# main.net
KiCad netlist of a schematic drawn in Altium Designer
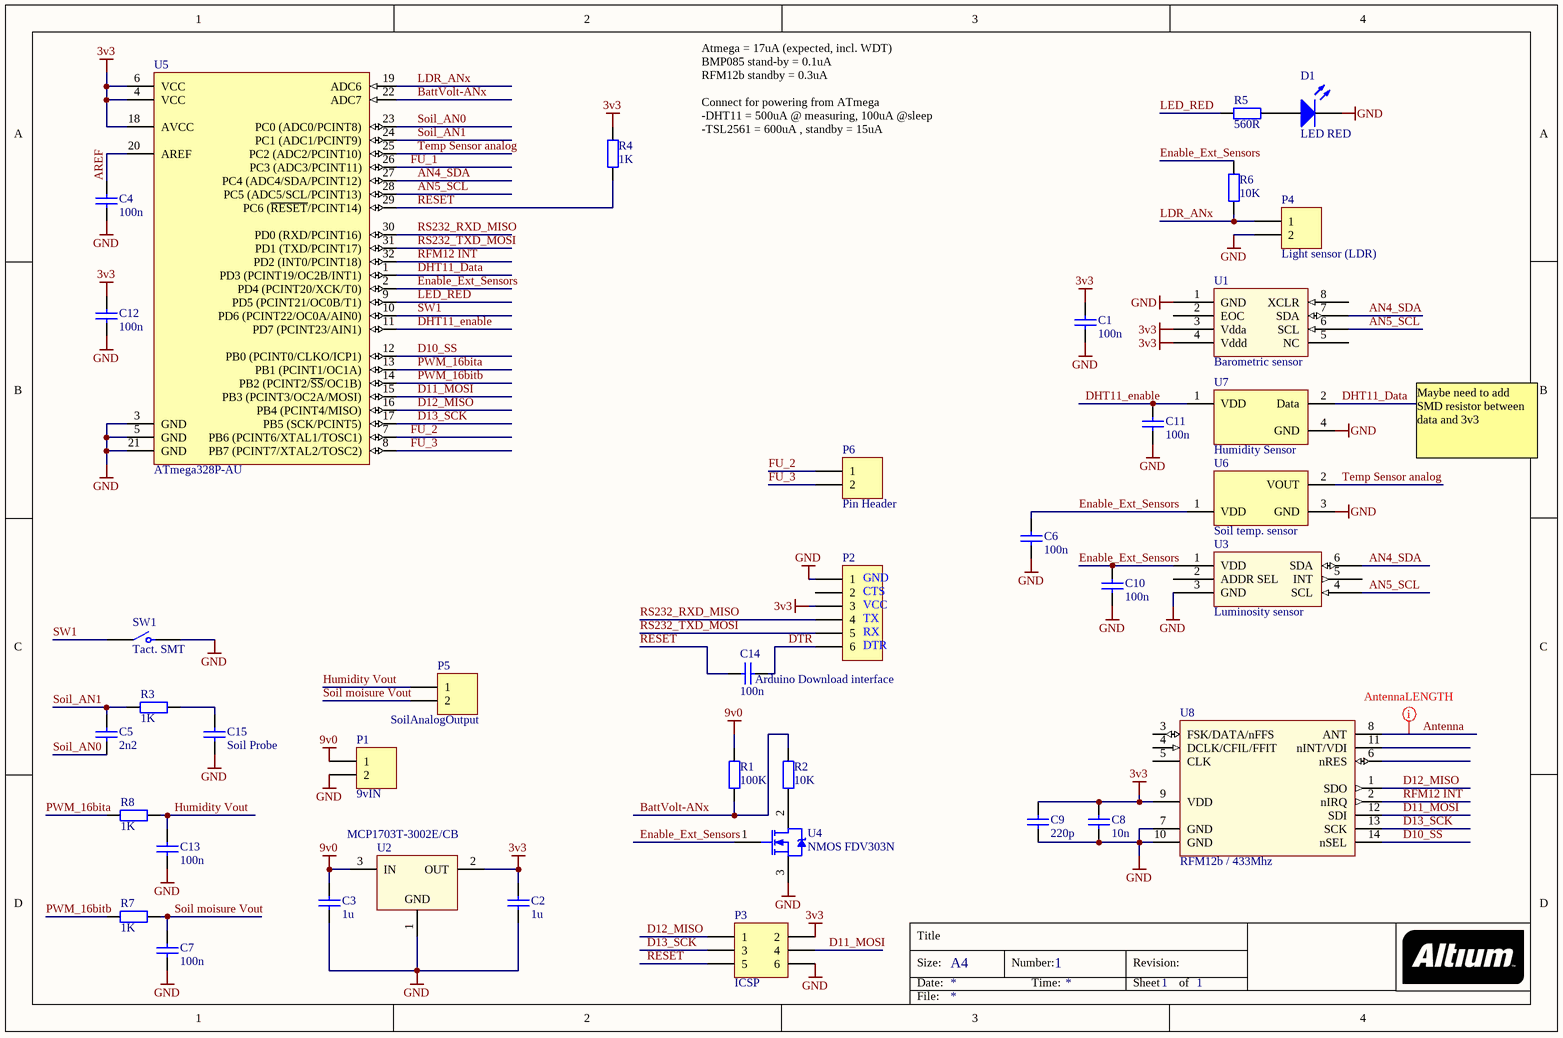
[diagram p0: main.SchDoc]

(export (version "E")
  (design (tool "Eeschema 10.0.6"))
  (components
    (comp (ref "C1") (value "100n") (footprint "C0805") (libsource (lib "OurDb") (part "cap_NonPolar")))
    (comp (ref "C2") (value "1u") (footprint "C0805") (libsource (lib "OurDb") (part "cap_NonPolar")))
    (comp (ref "C3") (value "1u") (footprint "C0805") (libsource (lib "OurDb") (part "cap_NonPolar")))
    (comp (ref "C4") (value "100n") (footprint "C0805") (libsource (lib "OurDb") (part "cap_NonPolar")))
    (comp (ref "C5") (value "2n2") (footprint "C0805") (libsource (lib "OurDb") (part "cap_NonPolar")))
    (comp (ref "C6") (value "100n") (footprint "C0805") (libsource (lib "OurDb") (part "cap_NonPolar")))
    (comp (ref "C7") (value "100n") (footprint "C0805") (libsource (lib "OurDb") (part "cap_NonPolar")))
    (comp (ref "C8") (value "10n") (footprint "C0805") (libsource (lib "OurDb") (part "cap_NonPolar")))
    (comp (ref "C9") (value "220p") (footprint "C0805") (libsource (lib "OurDb") (part "cap_NonPolar")))
    (comp (ref "C10") (value "100n") (footprint "C0805") (libsource (lib "OurDb") (part "cap_NonPolar")))
    (comp (ref "C11") (value "100n") (footprint "C0805") (libsource (lib "OurDb") (part "cap_NonPolar")))
    (comp (ref "C12") (value "100n") (footprint "C0805") (libsource (lib "OurDb") (part "cap_NonPolar")))
    (comp (ref "C13") (value "100n") (footprint "C0805") (libsource (lib "OurDb") (part "cap_NonPolar")))
    (comp (ref "C14") (value "100n") (footprint "C0805") (libsource (lib "OurDb") (part "cap_NonPolar")))
    (comp (ref "C15")
      (value "Soil Probe")
      (footprint "C0805")
      (fields (field (name "PART NUMBER") "18p"))
      (libsource (lib "OurDb") (part "cap_NonPolar"))
    )
    (comp (ref "D1")
      (value "LED RED")
      (footprint "LED-3mm")
      (description "LED, Surface Mount LED Indicator")
      (fields (field (name "PART NUMBER") "Red-3mm"))
      (libsource (lib "OurDb") (part "LED_SINGLE"))
    )
    (comp (ref "P1")
      (value "9vIN")
      (footprint "PH1x2_2.54")
      (description "Con1x2")
      (fields (field (name "PART NUMBER") "PH1x2"))
      (libsource (lib "OurDb") (part "Con1x2"))
    )
    (comp (ref "P2")
      (value "Arduino Download interface")
      (footprint "PH1x6_2.54")
      (description "Con1x6")
      (fields (field (name "PART NUMBER") "PH1x6"))
      (libsource (lib "OurDb") (part "Con1x6"))
    )
    (comp (ref "P3")
      (value "ICSP")
      (footprint "PH2x3_2.54")
      (description "Header, 3-Pin, Dual row")
      (fields (field (name "PART NUMBER") "PH2x3"))
      (libsource (lib "OurDb") (part "Con2x3"))
    )
    (comp (ref "P4")
      (value "Light sensor (LDR)")
      (footprint "PH1x2_2.54")
      (description "Con1x2")
      (fields (field (name "PART NUMBER") "PH1x2"))
      (libsource (lib "OurDb") (part "Con1x2"))
    )
    (comp (ref "P5")
      (value "SoilAnalogOutput")
      (footprint "PH1x2_2.54")
      (description "Con1x2")
      (fields (field (name "PART NUMBER") "PH1x2"))
      (libsource (lib "OurDb") (part "Con1x2"))
    )
    (comp (ref "P6")
      (value "Pin Header")
      (footprint "PH1x2_2.54")
      (description "Con1x2")
      (fields (field (name "PART NUMBER") "PH1x2") (field (name "AUTHOR") "Willy Pietersz"))
      (libsource (lib "OurDb") (part "Con1x2"))
    )
    (comp (ref "R1")
      (value "RESISTOR")
      (footprint "R0805")
      (description "Resistor")
      (fields (field (name "PART NUMBER") "100K") (field (name "PUBLISHER") "Altium Limited"))
      (libsource (lib "OurDb") (part "RESISTOR"))
    )
    (comp (ref "R2")
      (value "RESISTOR")
      (footprint "R0805")
      (description "Resistor")
      (fields (field (name "PART NUMBER") "10K") (field (name "PUBLISHER") "Altium Limited"))
      (libsource (lib "") (part "RESISTOR_3"))
    )
    (comp (ref "R3")
      (value "RESISTOR")
      (footprint "R0805")
      (description "Resistor")
      (fields (field (name "PART NUMBER") "1K") (field (name "PUBLISHER") "Altium Limited"))
      (libsource (lib "") (part "RESISTOR_1"))
    )
    (comp (ref "R4")
      (value "RESISTOR")
      (footprint "R0805")
      (description "Resistor")
      (fields (field (name "PART NUMBER") "1K") (field (name "PUBLISHER") "Altium Limited"))
      (libsource (lib "OurDb") (part "RESISTOR"))
    )
    (comp (ref "R5")
      (value "RESISTOR")
      (footprint "R0805")
      (description "Resistor")
      (fields (field (name "PART NUMBER") "560R") (field (name "PUBLISHER") "Altium Limited"))
      (libsource (lib "") (part "RESISTOR_2"))
    )
    (comp (ref "R6")
      (value "RESISTOR")
      (footprint "R0805")
      (description "Resistor")
      (fields (field (name "PART NUMBER") "10K") (field (name "PUBLISHER") "Altium Limited"))
      (libsource (lib "OurDb") (part "RESISTOR"))
    )
    (comp (ref "R7")
      (value "RESISTOR")
      (footprint "R0805")
      (description "Resistor")
      (fields (field (name "PART NUMBER") "1K") (field (name "PUBLISHER") "Altium Limited"))
      (libsource (lib "") (part "RESISTOR_1"))
    )
    (comp (ref "R8")
      (value "RESISTOR")
      (footprint "R0805")
      (description "Resistor")
      (fields (field (name "PART NUMBER") "1K") (field (name "PUBLISHER") "Altium Limited"))
      (libsource (lib "") (part "RESISTOR_1"))
    )
    (comp (ref "SW1")
      (value "Tact. SMT")
      (footprint "Switch TACT 3.5*6")
      (description "Switch")
      (fields
        (field (name "PART NUMBER") "Pushbutton TACT mini 3.5x6")
        (field (name "VOLTAGE") "42")
        (field (name "AUTHOR") "Willem Pietersz")
      )
      (libsource (lib "OurDb") (part "SW-TACT 2p"))
    )
    (comp (ref "U1")
      (value "Barometric sensor")
      (footprint "BMP085")
      (description "Sensor, Barometric")
      (fields (field (name "PART NUMBER") "BMP085"))
      (libsource (lib "OurDb") (part "BMP085"))
    )
    (comp (ref "U2")
      (value "MCP1703T")
      (footprint "SOT23")
      (description "Regulator, 5v")
      (fields (field (name "PART NUMBER") "MCP1703T-3002E/CB"))
      (libsource (lib "OurDb") (part "AMS1117"))
    )
    (comp (ref "U3")
      (value "Luminosity sensor")
      (footprint "TSL2561")
      (description "Sensor, Illumination")
      (fields (field (name "PART NUMBER") "TSL2561"))
      (libsource (lib "OurDb") (part "TSL2561"))
    )
    (comp (ref "U4")
      (value "NMOS FDV303N")
      (footprint "SOT-23-FET")
      (description "Transistor")
      (fields (field (name "PART NUMBER") "FDV303N"))
      (libsource (lib "OurDb") (part "NMOS"))
    )
    (comp (ref "U5")
      (value "ATmega328P-AU")
      (footprint "atmel_32A_N")
      (fields (field (name "PUBLISHER") "Altium Limited"))
      (libsource (lib "AltiumDatabaseSelection") (part "ATmega328P-AU"))
    )
    (comp (ref "U6")
      (value "Soil temp. sensor")
      (footprint "SOT-23-TT3_M")
      (description "Low-Power Linear Active Thermistor IC, 3-Pin SOT-23, Extended Temperature, Tape and Reel")
      (fields (field (name "PART NUMBER") "MCP9700AT-E/TT"))
      (libsource (lib "OurDb") (part "MCP9700AT-E/TT"))
    )
    (comp (ref "U7")
      (value "Humidity Sensor")
      (footprint "DHTXX")
      (description "Humidity / Temp Sensor")
      (fields (field (name "PART NUMBER") "DHT11"))
      (libsource (lib "OurDb") (part "DHT11"))
    )
    (comp (ref "U8")
      (value "RFM12b / 433Mhz")
      (footprint "RFM12_dev")
      (description "Wireless, Transceiver")
      (fields (field (name "PART NUMBER") "RFM12b"))
      (libsource (lib "OurDb") (part "RFM12B"))
    )
  )
  (nets
    (net (code "1") (name "/AN4_SDA") (class "Default")
      (node (ref "U1") (pin "7") (pinfunction "SDA_7") (pintype "bidirectional"))
      (node (ref "U3") (pin "6") (pinfunction "SDA_6") (pintype "bidirectional"))
      (node (ref "U5") (pin "27") (pinfunction "PC4_(ADC4/SDA/PCINT12)_27") (pintype "bidirectional"))
    )
    (net (code "2") (name "/AN5_SCL") (class "Default")
      (node (ref "U1") (pin "6") (pinfunction "SCL_6") (pintype "input"))
      (node (ref "U3") (pin "4") (pinfunction "SCL_4") (pintype "input"))
      (node (ref "U5") (pin "28") (pinfunction "PC5_(ADC5/SCL/PCINT13)_28") (pintype "bidirectional"))
    )
    (net (code "3") (name "/AREF") (class "Default")
      (node (ref "C4") (pin "2") (pinfunction "2_2") (pintype "passive"))
      (node (ref "U5") (pin "20") (pinfunction "AREF_20") (pintype "passive"))
    )
    (net (code "4") (name "/Antenna") (class "Default")
      (node (ref "U8") (pin "8") (pinfunction "ANT_8") (pintype "power_in"))
    )
    (net (code "5") (name "/BattVolt-ANx") (class "Default")
      (node (ref "R1") (pin "2") (pinfunction "2_2") (pintype "passive"))
      (node (ref "R2") (pin "2") (pinfunction "2_2") (pintype "passive"))
      (node (ref "U5") (pin "22") (pinfunction "ADC7_22") (pintype "input"))
    )
    (net (code "6") (name "/D10_SS") (class "Default")
      (node (ref "U5") (pin "12") (pinfunction "PB0_(PCINT0/CLKO/ICP1)_12") (pintype "bidirectional"))
      (node (ref "U8") (pin "14") (pinfunction "nSEL_14") (pintype "passive"))
    )
    (net (code "7") (name "/D11_MOSI") (class "Default")
      (node (ref "P3") (pin "4") (pinfunction "4_4") (pintype "passive"))
      (node (ref "U5") (pin "15") (pinfunction "PB3_(PCINT3/OC2A/MOSI)_15") (pintype "bidirectional"))
      (node (ref "U8") (pin "12") (pinfunction "SDI_12") (pintype "passive"))
    )
    (net (code "8") (name "/D12_MISO") (class "Default")
      (node (ref "P3") (pin "1") (pinfunction "1_1") (pintype "passive"))
      (node (ref "U5") (pin "16") (pinfunction "PB4_(PCINT4/MISO)_16") (pintype "bidirectional"))
      (node (ref "U8") (pin "1") (pinfunction "SDO_1") (pintype "output"))
    )
    (net (code "9") (name "/D13_SCK") (class "Default")
      (node (ref "P3") (pin "3") (pinfunction "3_3") (pintype "passive"))
      (node (ref "U5") (pin "17") (pinfunction "PB5_(SCK/PCINT5)_17") (pintype "bidirectional"))
      (node (ref "U8") (pin "13") (pinfunction "SCK_13") (pintype "passive"))
    )
    (net (code "10") (name "/DHT11_Data") (class "Default")
      (node (ref "U5") (pin "1") (pinfunction "PD3_(PCINT19/OC2B/INT1)_1") (pintype "bidirectional"))
      (node (ref "U7") (pin "2") (pinfunction "Data_2") (pintype "power_in"))
    )
    (net (code "11") (name "/DHT11_enable") (class "Default")
      (node (ref "C11") (pin "2") (pinfunction "2_2") (pintype "passive"))
      (node (ref "U5") (pin "11") (pinfunction "PD7_(PCINT23/AIN1)_11") (pintype "bidirectional"))
      (node (ref "U7") (pin "1") (pinfunction "VDD_1") (pintype "power_in"))
    )
    (net (code "12") (name "/DTR") (class "Default")
      (node (ref "C14") (pin "2") (pinfunction "2_2") (pintype "passive"))
      (node (ref "P2") (pin "6") (pinfunction "6_6") (pintype "passive"))
    )
    (net (code "13") (name "/Enable_Ext_Sensors") (class "Default")
      (node (ref "C10") (pin "2") (pinfunction "2_2") (pintype "passive"))
      (node (ref "C6") (pin "2") (pinfunction "2_2") (pintype "passive"))
      (node (ref "R6") (pin "1") (pinfunction "1_1") (pintype "passive"))
      (node (ref "U3") (pin "1") (pinfunction "VDD_1") (pintype "power_in"))
      (node (ref "U4") (pin "1") (pinfunction "G_1") (pintype "passive"))
      (node (ref "U5") (pin "2") (pinfunction "PD4_(PCINT20/XCK/T0)_2") (pintype "bidirectional"))
      (node (ref "U6") (pin "1") (pinfunction "VDD_1") (pintype "power_in"))
    )
    (net (code "14") (name "/FU_1") (class "Default")
      (node (ref "U5") (pin "26") (pinfunction "PC3_(ADC3/PCINT11)_26") (pintype "bidirectional"))
    )
    (net (code "15") (name "/FU_2") (class "Default")
      (node (ref "P6") (pin "1") (pinfunction "1_1") (pintype "passive"))
      (node (ref "U5") (pin "7") (pinfunction "PB6_(PCINT6/XTAL1/TOSC1)_7") (pintype "bidirectional"))
    )
    (net (code "16") (name "/FU_3") (class "Default")
      (node (ref "P6") (pin "2") (pinfunction "2_2") (pintype "passive"))
      (node (ref "U5") (pin "8") (pinfunction "PB7_(PCINT7/XTAL2/TOSC2)_8") (pintype "bidirectional"))
    )
    (net (code "17") (name "/Humidity Vout") (class "Default")
      (node (ref "C13") (pin "2") (pinfunction "2_2") (pintype "passive"))
      (node (ref "P5") (pin "1") (pinfunction "1_1") (pintype "passive"))
      (node (ref "R8") (pin "1") (pinfunction "1_1") (pintype "passive"))
    )
    (net (code "18") (name "/LDR_ANx") (class "Default")
      (node (ref "P4") (pin "1") (pinfunction "1_1") (pintype "passive"))
      (node (ref "R6") (pin "2") (pinfunction "2_2") (pintype "passive"))
      (node (ref "U5") (pin "19") (pinfunction "ADC6_19") (pintype "input"))
    )
    (net (code "19") (name "/LED_RED") (class "Default")
      (node (ref "R5") (pin "1") (pinfunction "1_1") (pintype "passive"))
      (node (ref "U5") (pin "9") (pinfunction "PD5_(PCINT21/OC0B/T1)_9") (pintype "bidirectional"))
    )
    (net (code "20") (name "/PWM_16bita") (class "Default")
      (node (ref "R8") (pin "2") (pinfunction "2_2") (pintype "passive"))
      (node (ref "U5") (pin "13") (pinfunction "PB1_(PCINT1/OC1A)_13") (pintype "bidirectional"))
    )
    (net (code "21") (name "/PWM_16bitb") (class "Default")
      (node (ref "R7") (pin "2") (pinfunction "2_2") (pintype "passive"))
      (node (ref "U5") (pin "14") (pinfunction "PB2_(PCINT2/~{SS}/OC1B)_14") (pintype "bidirectional"))
    )
    (net (code "22") (name "/RESET") (class "Default")
      (node (ref "C14") (pin "1") (pinfunction "1_1") (pintype "passive"))
      (node (ref "P3") (pin "5") (pinfunction "5_5") (pintype "passive"))
      (node (ref "R4") (pin "2") (pinfunction "2_2") (pintype "passive"))
      (node (ref "U5") (pin "29") (pinfunction "PC6_(~{RESET}/PCINT14)_29") (pintype "bidirectional"))
    )
    (net (code "23") (name "/RFM12 INT") (class "Default")
      (node (ref "U5") (pin "32") (pinfunction "PD2_(INT0/PCINT18)_32") (pintype "bidirectional"))
      (node (ref "U8") (pin "2") (pinfunction "nIRQ_2") (pintype "output"))
    )
    (net (code "24") (name "/RS232_RXD_MISO") (class "Default")
      (node (ref "P2") (pin "4") (pinfunction "4_4") (pintype "passive"))
      (node (ref "U5") (pin "30") (pinfunction "PD0_(RXD/PCINT16)_30") (pintype "bidirectional"))
    )
    (net (code "25") (name "/RS232_TXD_MOSI") (class "Default")
      (node (ref "P2") (pin "5") (pinfunction "5_5") (pintype "passive"))
      (node (ref "U5") (pin "31") (pinfunction "PD1_(TXD/PCINT17)_31") (pintype "bidirectional"))
    )
    (net (code "26") (name "/SW1") (class "Default")
      (node (ref "SW1") (pin "1") (pintype "passive"))
      (node (ref "U5") (pin "10") (pinfunction "PD6_(PCINT22/OC0A/AIN0)_10") (pintype "bidirectional"))
    )
    (net (code "27") (name "/Soil moisure Vout") (class "Default")
      (node (ref "C7") (pin "2") (pinfunction "2_2") (pintype "passive"))
      (node (ref "P5") (pin "2") (pinfunction "2_2") (pintype "passive"))
      (node (ref "R7") (pin "1") (pinfunction "1_1") (pintype "passive"))
    )
    (net (code "28") (name "/Soil_AN0") (class "Default")
      (node (ref "C5") (pin "1") (pinfunction "1_1") (pintype "passive"))
      (node (ref "U5") (pin "23") (pinfunction "PC0_(ADC0/PCINT8)_23") (pintype "bidirectional"))
    )
    (net (code "29") (name "/Soil_AN1") (class "Default")
      (node (ref "C5") (pin "2") (pinfunction "2_2") (pintype "passive"))
      (node (ref "R3") (pin "2") (pinfunction "2_2") (pintype "passive"))
      (node (ref "U5") (pin "24") (pinfunction "PC1_(ADC1/PCINT9)_24") (pintype "bidirectional"))
    )
    (net (code "30") (name "/Temp Sensor analog") (class "Default")
      (node (ref "U5") (pin "25") (pinfunction "PC2_(ADC2/PCINT10)_25") (pintype "bidirectional"))
      (node (ref "U6") (pin "2") (pinfunction "VOUT_2") (pintype "power_in"))
    )
    (net (code "31") (name "3v3") (class "Default")
      (node (ref "C1") (pin "2") (pinfunction "2_2") (pintype "passive"))
      (node (ref "C12") (pin "2") (pinfunction "2_2") (pintype "passive"))
      (node (ref "C2") (pin "2") (pinfunction "2_2") (pintype "passive"))
      (node (ref "C8") (pin "2") (pinfunction "2_2") (pintype "passive"))
      (node (ref "C9") (pin "2") (pinfunction "2_2") (pintype "passive"))
      (node (ref "P2") (pin "3") (pinfunction "3_3") (pintype "passive"))
      (node (ref "P3") (pin "2") (pinfunction "2_2") (pintype "passive"))
      (node (ref "R4") (pin "1") (pinfunction "1_1") (pintype "passive"))
      (node (ref "U1") (pin "3") (pinfunction "Vdda_3") (pintype "power_in"))
      (node (ref "U1") (pin "4") (pinfunction "Vddd_4") (pintype "power_in"))
      (node (ref "U2") (pin "2") (pinfunction "OUT_2") (pintype "power_in"))
      (node (ref "U5") (pin "18") (pinfunction "AVCC_18") (pintype "power_in"))
      (node (ref "U5") (pin "4") (pinfunction "VCC_4") (pintype "power_in"))
      (node (ref "U5") (pin "6") (pinfunction "VCC_6") (pintype "power_in"))
      (node (ref "U8") (pin "9") (pinfunction "VDD_9") (pintype "power_in"))
    )
    (net (code "32") (name "9v0") (class "Default")
      (node (ref "C3") (pin "2") (pinfunction "2_2") (pintype "passive"))
      (node (ref "P1") (pin "1") (pinfunction "1_1") (pintype "passive"))
      (node (ref "R1") (pin "1") (pinfunction "1_1") (pintype "passive"))
      (node (ref "U2") (pin "3") (pinfunction "IN_3") (pintype "passive"))
    )
    (net (code "33") (name "GND") (class "Default")
      (node (ref "C1") (pin "1") (pinfunction "1_1") (pintype "passive"))
      (node (ref "C10") (pin "1") (pinfunction "1_1") (pintype "passive"))
      (node (ref "C11") (pin "1") (pinfunction "1_1") (pintype "passive"))
      (node (ref "C12") (pin "1") (pinfunction "1_1") (pintype "passive"))
      (node (ref "C13") (pin "1") (pinfunction "1_1") (pintype "passive"))
      (node (ref "C15") (pin "1") (pinfunction "1_1") (pintype "passive"))
      (node (ref "C2") (pin "1") (pinfunction "1_1") (pintype "passive"))
      (node (ref "C3") (pin "1") (pinfunction "1_1") (pintype "passive"))
      (node (ref "C4") (pin "1") (pinfunction "1_1") (pintype "passive"))
      (node (ref "C6") (pin "1") (pinfunction "1_1") (pintype "passive"))
      (node (ref "C7") (pin "1") (pinfunction "1_1") (pintype "passive"))
      (node (ref "C8") (pin "1") (pinfunction "1_1") (pintype "passive"))
      (node (ref "C9") (pin "1") (pinfunction "1_1") (pintype "passive"))
      (node (ref "D1") (pin "2") (pinfunction "K_2") (pintype "passive"))
      (node (ref "P1") (pin "2") (pinfunction "2_2") (pintype "passive"))
      (node (ref "P2") (pin "1") (pinfunction "1_1") (pintype "passive"))
      (node (ref "P3") (pin "6") (pinfunction "6_6") (pintype "passive"))
      (node (ref "P4") (pin "2") (pinfunction "2_2") (pintype "passive"))
      (node (ref "SW1") (pin "2") (pintype "passive"))
      (node (ref "U1") (pin "1") (pinfunction "GND_1") (pintype "power_in"))
      (node (ref "U2") (pin "1") (pinfunction "GND_1") (pintype "passive"))
      (node (ref "U3") (pin "3") (pinfunction "GND_3") (pintype "power_in"))
      (node (ref "U4") (pin "3") (pinfunction "S_3") (pintype "passive"))
      (node (ref "U5") (pin "21") (pinfunction "GND_21") (pintype "power_in"))
      (node (ref "U5") (pin "3") (pinfunction "GND_3") (pintype "power_in"))
      (node (ref "U5") (pin "5") (pinfunction "GND_5") (pintype "power_in"))
      (node (ref "U6") (pin "3") (pinfunction "GND_3") (pintype "power_in"))
      (node (ref "U7") (pin "4") (pinfunction "GND_4") (pintype "power_in"))
      (node (ref "U8") (pin "10") (pinfunction "GND_10") (pintype "power_in"))
      (node (ref "U8") (pin "7") (pinfunction "GND_7") (pintype "power_in"))
    )
    (net (code "34") (name "Net-(C15-Pad2)") (class "Default")
      (node (ref "C15") (pin "2") (pinfunction "2_2") (pintype "passive"))
      (node (ref "R3") (pin "1") (pinfunction "1_1") (pintype "passive"))
    )
    (net (code "35") (name "Net-(D1-A)") (class "Default")
      (node (ref "D1") (pin "1") (pinfunction "A_1") (pintype "passive"))
      (node (ref "R5") (pin "2") (pinfunction "2_2") (pintype "passive"))
    )
    (net (code "36") (name "Net-(U4-D)") (class "Default")
      (node (ref "R2") (pin "1") (pinfunction "1_1") (pintype "passive"))
      (node (ref "U4") (pin "2") (pinfunction "D_2") (pintype "passive"))
    )
    (net (code "37") (name "unconnected-(P2-Pad2)") (class "Default")
      (node (ref "P2") (pin "2") (pinfunction "2_2") (pintype "passive"))
    )
    (net (code "38") (name "unconnected-(U1-EOC-Pad2)") (class "Default")
      (node (ref "U1") (pin "2") (pinfunction "EOC_2") (pintype "passive"))
    )
    (net (code "39") (name "unconnected-(U1-NC-Pad5)") (class "Default")
      (node (ref "U1") (pin "5") (pinfunction "NC_5") (pintype "passive"))
    )
    (net (code "40") (name "unconnected-(U1-XCLR-Pad8)") (class "Default")
      (node (ref "U1") (pin "8") (pinfunction "XCLR_8") (pintype "input"))
    )
    (net (code "41") (name "unconnected-(U3-ADDR_SEL-Pad2)") (class "Default")
      (node (ref "U3") (pin "2") (pinfunction "ADDR_SEL_2") (pintype "passive"))
    )
    (net (code "42") (name "unconnected-(U3-INT-Pad5)") (class "Default")
      (node (ref "U3") (pin "5") (pinfunction "INT_5") (pintype "output"))
    )
    (net (code "43") (name "unconnected-(U8-CLK-Pad5)") (class "Default")
      (node (ref "U8") (pin "5") (pinfunction "CLK_5") (pintype "power_in"))
    )
    (net (code "44") (name "unconnected-(U8-DCLK{slash}CFIL{slash}FFIT-Pad4)") (class "Default")
      (node (ref "U8") (pin "4") (pinfunction "DCLK/CFIL/FFIT_4") (pintype "input"))
    )
    (net (code "45") (name "unconnected-(U8-FSK{slash}DATA{slash}nFFS-Pad3)") (class "Default")
      (node (ref "U8") (pin "3") (pinfunction "FSK/DATA/nFFS_3") (pintype "bidirectional"))
    )
    (net (code "46") (name "unconnected-(U8-nINT{slash}VDI-Pad11)") (class "Default")
      (node (ref "U8") (pin "11") (pinfunction "nINT/VDI_11") (pintype "passive"))
    )
    (net (code "47") (name "unconnected-(U8-nRES-Pad6)") (class "Default")
      (node (ref "U8") (pin "6") (pinfunction "nRES_6") (pintype "bidirectional"))
    )
  )
)
